# USB.net
KiCad netlist of a schematic drawn in Altium Designer
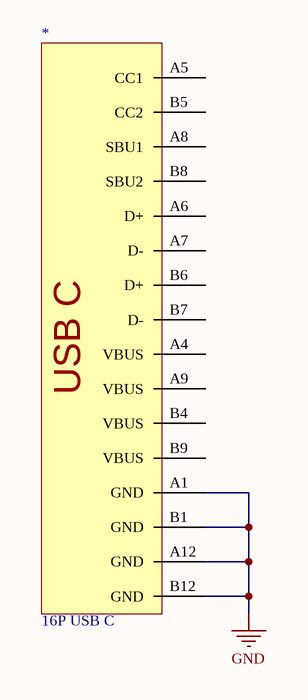
[diagram p0: USB.SchDoc]

(export (version "E")
  (design (tool "Eeschema 10.0.6"))
  (components
    (comp (ref "*")
      (value "16P USB C")
      (description "USB - C Receptacle Connector 16 Position smt")
      (fields
        (field (name "MANUFACTURER") "risym")
        (field (name "MANUFACTURER PART NUMBER") "TYPE-CF-16P-OT1.6-L6.5")
      )
      (libsource (lib "USB_Sch") (part "16P USB C"))
    )
  )
  (nets
    (net (code "1") (name "GND") (class "Default")
      (node (ref "*") (pin "A1") (pinfunction "GND_A1") (pintype "passive"))
      (node (ref "*") (pin "A12") (pinfunction "GND_A12") (pintype "passive"))
      (node (ref "*") (pin "B1") (pinfunction "GND_B1") (pintype "passive"))
      (node (ref "*") (pin "B12") (pinfunction "GND_B12") (pintype "passive"))
    )
    (net (code "2") (name "unconnected-(*-CC1-PadA5)") (class "Default")
      (node (ref "*") (pin "A5") (pinfunction "CC1_A5") (pintype "passive"))
    )
    (net (code "3") (name "unconnected-(*-CC2-PadB5)") (class "Default")
      (node (ref "*") (pin "B5") (pinfunction "CC2_B5") (pintype "passive"))
    )
    (net (code "4") (name "unconnected-(*-D+-PadA6)") (class "Default")
      (node (ref "*") (pin "A6") (pinfunction "D+_A6") (pintype "passive"))
    )
    (net (code "5") (name "unconnected-(*-D+-PadB6)") (class "Default")
      (node (ref "*") (pin "B6") (pinfunction "D+_B6") (pintype "passive"))
    )
    (net (code "6") (name "unconnected-(*-D--PadA7)") (class "Default")
      (node (ref "*") (pin "A7") (pinfunction "D-_A7") (pintype "passive"))
    )
    (net (code "7") (name "unconnected-(*-D--PadB7)") (class "Default")
      (node (ref "*") (pin "B7") (pinfunction "D-_B7") (pintype "passive"))
    )
    (net (code "8") (name "unconnected-(*-SBU1-PadA8)") (class "Default")
      (node (ref "*") (pin "A8") (pinfunction "SBU1_A8") (pintype "passive"))
    )
    (net (code "9") (name "unconnected-(*-SBU2-PadB8)") (class "Default")
      (node (ref "*") (pin "B8") (pinfunction "SBU2_B8") (pintype "passive"))
    )
    (net (code "10") (name "unconnected-(*-VBUS-PadA4)") (class "Default")
      (node (ref "*") (pin "A4") (pinfunction "VBUS_A4") (pintype "passive"))
    )
    (net (code "11") (name "unconnected-(*-VBUS-PadA9)") (class "Default")
      (node (ref "*") (pin "A9") (pinfunction "VBUS_A9") (pintype "passive"))
    )
    (net (code "12") (name "unconnected-(*-VBUS-PadB4)") (class "Default")
      (node (ref "*") (pin "B4") (pinfunction "VBUS_B4") (pintype "passive"))
    )
    (net (code "13") (name "unconnected-(*-VBUS-PadB9)") (class "Default")
      (node (ref "*") (pin "B9") (pinfunction "VBUS_B9") (pintype "passive"))
    )
  )
)
